# rda5807m.net
KiCad netlist of a schematic drawn in EAGLE
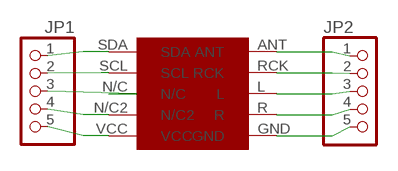
[diagram p0: schematic, sheet 1]

(export (version "E")
  (design (tool "Eeschema 10.0.6"))
  (components
    (comp (ref "JP1")
      (value "PINHD-1X5")
      (footprint "eagle-import:1X05")
      (libsource (lib "eagle-import") (part "PINHD-1X5"))
    )
    (comp (ref "JP2")
      (value "PINHD-1X5")
      (footprint "eagle-import:1X05")
      (libsource (lib "eagle-import") (part "PINHD-1X5"))
    )
    (comp (ref "U$1")
      (value "RDA")
      (footprint "eagle-import:RDA")
      (libsource (lib "eagle-import") (part "RDA"))
    )
  )
  (nets
    (net (code "1") (name "Net-(JP1-Pad1)") (class "Default")
      (node (ref "JP1") (pin "1") (pinfunction "1_1") (pintype "passive"))
      (node (ref "U$1") (pin "SDA") (pinfunction "SDA_SDA") (pintype "bidirectional"))
    )
    (net (code "2") (name "Net-(JP1-Pad2)") (class "Default")
      (node (ref "JP1") (pin "2") (pinfunction "2_2") (pintype "passive"))
      (node (ref "U$1") (pin "SCL") (pinfunction "SCL_SCL") (pintype "bidirectional"))
    )
    (net (code "3") (name "Net-(JP1-Pad3)") (class "Default")
      (node (ref "JP1") (pin "3") (pinfunction "3_3") (pintype "passive"))
      (node (ref "U$1") (pin "N/C") (pinfunction "N/C_N/C") (pintype "passive"))
    )
    (net (code "4") (name "Net-(JP1-Pad4)") (class "Default")
      (node (ref "JP1") (pin "4") (pinfunction "4_4") (pintype "passive"))
      (node (ref "U$1") (pin "N/C2") (pinfunction "N/C2_N/C2") (pintype "passive"))
    )
    (net (code "5") (name "Net-(JP1-Pad5)") (class "Default")
      (node (ref "JP1") (pin "5") (pinfunction "5_5") (pintype "passive"))
      (node (ref "U$1") (pin "VCC") (pinfunction "VCC_VCC") (pintype "power_in"))
    )
    (net (code "6") (name "Net-(JP2-Pad1)") (class "Default")
      (node (ref "JP2") (pin "1") (pinfunction "1_1") (pintype "passive"))
      (node (ref "U$1") (pin "ANT") (pinfunction "ANT_ANT") (pintype "input"))
    )
    (net (code "7") (name "Net-(JP2-Pad2)") (class "Default")
      (node (ref "JP2") (pin "2") (pinfunction "2_2") (pintype "passive"))
      (node (ref "U$1") (pin "RCK") (pinfunction "RCK_RCK") (pintype "bidirectional"))
    )
    (net (code "8") (name "Net-(JP2-Pad3)") (class "Default")
      (node (ref "JP2") (pin "3") (pinfunction "3_3") (pintype "passive"))
      (node (ref "U$1") (pin "L") (pinfunction "L_L") (pintype "output"))
    )
    (net (code "9") (name "Net-(JP2-Pad4)") (class "Default")
      (node (ref "JP2") (pin "4") (pinfunction "4_4") (pintype "passive"))
      (node (ref "U$1") (pin "R") (pinfunction "R_R") (pintype "output"))
    )
    (net (code "10") (name "Net-(JP2-Pad5)") (class "Default")
      (node (ref "JP2") (pin "5") (pinfunction "5_5") (pintype "passive"))
      (node (ref "U$1") (pin "GND") (pinfunction "GND_GND") (pintype "power_in"))
    )
  )
)
